# Modulo_de_apertura_Power.net
KiCad netlist of a schematic drawn in Altium Designer
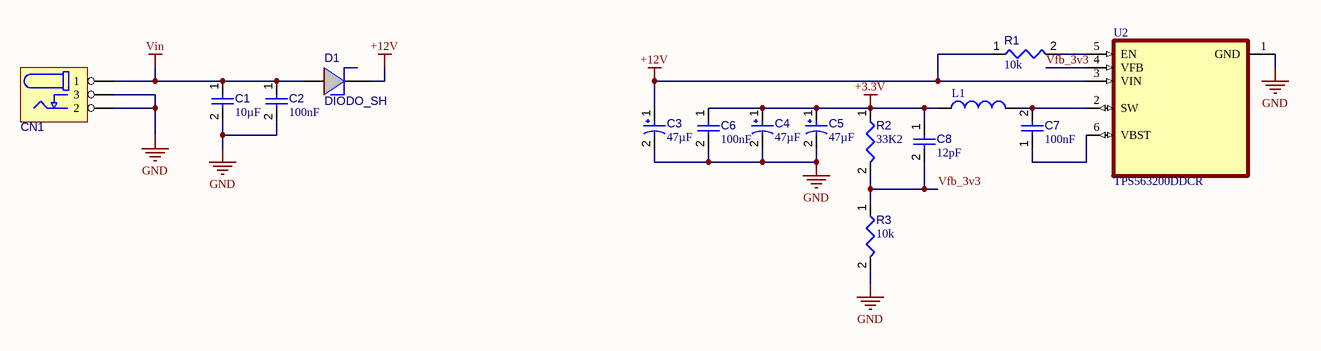
[diagram p0: Modulo_de_apertura_Power.SchDoc]

(export (version "E")
  (design (tool "Eeschema 10.0.6"))
  (components
    (comp (ref "C1")
      (value "10µF")
      (footprint "CAPC0603(1608)100_L")
      (description "Chip Capacitor, 10µF +/-20%, 10V, 0603, Thickness 1 mm")
      (fields (field (name "TOLERANCE") "10%") (field (name "Comment") "Capacitor 10µF +/-20% 10V 0603"))
      (libsource (lib "Agustin Dubuisson") (part "CAP-NP-2"))
    )
    (comp (ref "C2")
      (value "100nF")
      (footprint "CAPC0402(1005)60_L")
      (description "Chip Capacitor, 100nF +/-20%, 10V, 0402, Thickness 0.6 mm")
      (fields (field (name "TOLERANCE") "20%") (field (name "Comment") "Capacitor 100nF +/-20% 10V 0402"))
      (libsource (lib "Agustin Dubuisson") (part "CAP-NP-2"))
    )
    (comp (ref "C3")
      (value "47µF")
      (footprint "CAPMP3217X18-T_V")
      (description "Standard Tantalum, 1 uF, +/- 10%, 35 V, -55 to 125 degC, 1206 (3216 Metric), RoHS, Tape and Reel")
      (fields (field (name "TOLERANCE") "10%") (field (name "MANUFACTURER") "AVX"))
      (libsource (lib "Agustin Dubuisson") (part "CAP-P-2"))
    )
    (comp (ref "C4")
      (value "47µF")
      (footprint "CAPMP3217X18-T_V")
      (description "Standard Tantalum, 1 uF, +/- 10%, 35 V, -55 to 125 degC, 1206 (3216 Metric), RoHS, Tape and Reel")
      (fields (field (name "TOLERANCE") "10%") (field (name "MANUFACTURER") "AVX"))
      (libsource (lib "Agustin Dubuisson") (part "CAP-P-2"))
    )
    (comp (ref "C5")
      (value "47µF")
      (footprint "CAPMP3217X18-T_V")
      (description "Standard Tantalum, 1 uF, +/- 10%, 35 V, -55 to 125 degC, 1206 (3216 Metric), RoHS, Tape and Reel")
      (fields (field (name "TOLERANCE") "10%") (field (name "MANUFACTURER") "AVX"))
      (libsource (lib "Agustin Dubuisson") (part "CAP-P-2"))
    )
    (comp (ref "C6")
      (value "100nF")
      (footprint "CAPC0402(1005)60_L")
      (description "Chip Capacitor, 100nF +/-20%, 50V, 0402, Thickness 0.6 mm")
      (fields (field (name "TOLERANCE") "10%") (field (name "Comment") "Capacitor 100nF +/-20% 50V 0402"))
      (libsource (lib "Agustin Dubuisson") (part "CAP-NP-2"))
    )
    (comp (ref "C7")
      (value "100nF")
      (footprint "CAPC0402(1005)60_L")
      (description "Chip Capacitor, 100nF +/-20%, 10V, 0402, Thickness 0.6 mm")
      (fields (field (name "TOLERANCE") "20%") (field (name "Comment") "Capacitor 100nF +/-20% 10V 0402"))
      (libsource (lib "Agustin Dubuisson") (part "CAP-NP-2"))
    )
    (comp (ref "C8")
      (value "12pF")
      (footprint "CAPC0402(1005)33_L")
      (description "Chip Capacitor, 12pF +/-10%, 50V, 0402, Thickness 0.33 mm")
      (fields (field (name "TOLERANCE") "20%") (field (name "Comment") "Capacitor 12pF +/-10% 50V 0402"))
      (libsource (lib "Agustin Dubuisson") (part "CAP-NP-2"))
    )
    (comp (ref "CN1")
      (value "CN_PowerJack")
      (footprint "PJ002B")
      (description "Barrel Power Connector")
      (libsource (lib "WifiNode") (part "CN_PowerJack"))
    )
    (comp (ref "D1")
      (value "DIODO_SH")
      (footprint "IDCI_WifiNode:D_SMA")
      (description "Diode Shottky")
      (libsource (lib "WifiNode") (part "DIODO_SH"))
    )
    (comp (ref "L1")
      (value "IFSC1515AHER2R2M01")
      (footprint "FP-IFSC1515AH-MFG")
      (description "General Purpose Inductor, 2.2uH, 20%, 1 Element, SMD, 1515")
      (fields (field (name "TOLERANCE") "20%"))
      (libsource (lib "Agustin Dubuisson") (part "IND-2"))
    )
    (comp (ref "R1")
      (value "10k")
      (footprint "RESC0402(1005)_L")
      (description "Chip Resistor, 10 kOhms, +/-1 %, 63 mW, -55 to 125 degC, 0402")
      (fields (field (name "POWER") "63mW") (field (name "TOLERANCE") "1%"))
      (libsource (lib "Agustin Dubuisson") (part "RES-2"))
    )
    (comp (ref "R2")
      (value "33K2")
      (footprint "RESC0402(1005)_L")
      (fields
        (field (name "POWER") "63mW")
        (field (name "TOLERANCE") "1%")
        (field (name "Comment") "Resistor 10K  +/-1 % 0402 63 mW")
      )
      (libsource (lib "Agustin Dubuisson") (part "RES-2"))
    )
    (comp (ref "R3")
      (value "10k")
      (footprint "RESC0402(1005)_L")
      (description "Chip Resistor, 10 kOhms, +/-1 %, 63 mW, -55 to 125 degC, 0402")
      (fields (field (name "POWER") "63mW") (field (name "TOLERANCE") "1%"))
      (libsource (lib "Agustin Dubuisson") (part "RES-2"))
    )
    (comp (ref "U2")
      (value "TPS563200DDCR")
      (footprint "SOT23-6")
      (description "17 V Input, 3A Synchronous Step-Down Regulator in SOT-23 with Advanced Eco-modeâ„¢")
      (fields (field (name "MF") "Texas Instruments"))
      (libsource (lib "TPS563200DDCR") (part "TPS563200DDCR"))
    )
  )
  (nets
    (net (code "1") (name "+3.3V") (class "Default")
      (node (ref "C4") (pin "1") (pinfunction "1_1") (pintype "passive"))
      (node (ref "C5") (pin "1") (pinfunction "1_1") (pintype "passive"))
      (node (ref "C6") (pin "1") (pinfunction "1_1") (pintype "passive"))
      (node (ref "C8") (pin "1") (pinfunction "1_1") (pintype "passive"))
      (node (ref "L1") (pin "1") (pinfunction "1_1") (pintype "passive"))
      (node (ref "R2") (pin "1") (pinfunction "1_1") (pintype "passive"))
    )
    (net (code "2") (name "+12V") (class "Default")
      (node (ref "C3") (pin "1") (pinfunction "1_1") (pintype "passive"))
      (node (ref "D1") (pin "2") (pinfunction "K_2") (pintype "passive"))
      (node (ref "R1") (pin "1") (pinfunction "1_1") (pintype "passive"))
      (node (ref "U2") (pin "3") (pinfunction "VIN_3") (pintype "input"))
    )
    (net (code "3") (name "/Vfb_3v3") (class "Default")
      (node (ref "C8") (pin "2") (pinfunction "2_2") (pintype "passive"))
      (node (ref "R2") (pin "2") (pinfunction "2_2") (pintype "passive"))
      (node (ref "R3") (pin "1") (pinfunction "1_1") (pintype "passive"))
      (node (ref "U2") (pin "4") (pinfunction "VFB_4") (pintype "input"))
    )
    (net (code "4") (name "GND") (class "Default")
      (node (ref "C1") (pin "2") (pinfunction "2_2") (pintype "passive"))
      (node (ref "C2") (pin "2") (pinfunction "2_2") (pintype "passive"))
      (node (ref "C3") (pin "2") (pinfunction "2_2") (pintype "passive"))
      (node (ref "C4") (pin "2") (pinfunction "2_2") (pintype "passive"))
      (node (ref "C5") (pin "2") (pinfunction "2_2") (pintype "passive"))
      (node (ref "C6") (pin "2") (pinfunction "2_2") (pintype "passive"))
      (node (ref "CN1") (pin "2") (pinfunction "2_2") (pintype "passive"))
      (node (ref "CN1") (pin "3") (pinfunction "3_3") (pintype "passive"))
      (node (ref "R3") (pin "2") (pinfunction "2_2") (pintype "passive"))
      (node (ref "U2") (pin "1") (pinfunction "GND_1") (pintype "power_in"))
    )
    (net (code "5") (name "Net-(U2-EN)") (class "Default")
      (node (ref "R1") (pin "2") (pinfunction "2_2") (pintype "passive"))
      (node (ref "U2") (pin "5") (pinfunction "EN_5") (pintype "input"))
    )
    (net (code "6") (name "Net-(U2-SW)") (class "Default")
      (node (ref "C7") (pin "2") (pinfunction "2_2") (pintype "passive"))
      (node (ref "L1") (pin "2") (pinfunction "2_2") (pintype "passive"))
      (node (ref "U2") (pin "2") (pinfunction "SW_2") (pintype "bidirectional"))
    )
    (net (code "7") (name "Net-(U2-VBST)") (class "Default")
      (node (ref "C7") (pin "1") (pinfunction "1_1") (pintype "passive"))
      (node (ref "U2") (pin "6") (pinfunction "VBST_6") (pintype "bidirectional"))
    )
    (net (code "8") (name "Vin") (class "Default")
      (node (ref "C1") (pin "1") (pinfunction "1_1") (pintype "passive"))
      (node (ref "C2") (pin "1") (pinfunction "1_1") (pintype "passive"))
      (node (ref "CN1") (pin "1") (pinfunction "1_1") (pintype "passive"))
      (node (ref "D1") (pin "1") (pinfunction "A_1") (pintype "passive"))
    )
  )
)
